# Omnimo_nRF52840_1v2.net
KiCad netlist of a schematic drawn in EasyEDA Pro
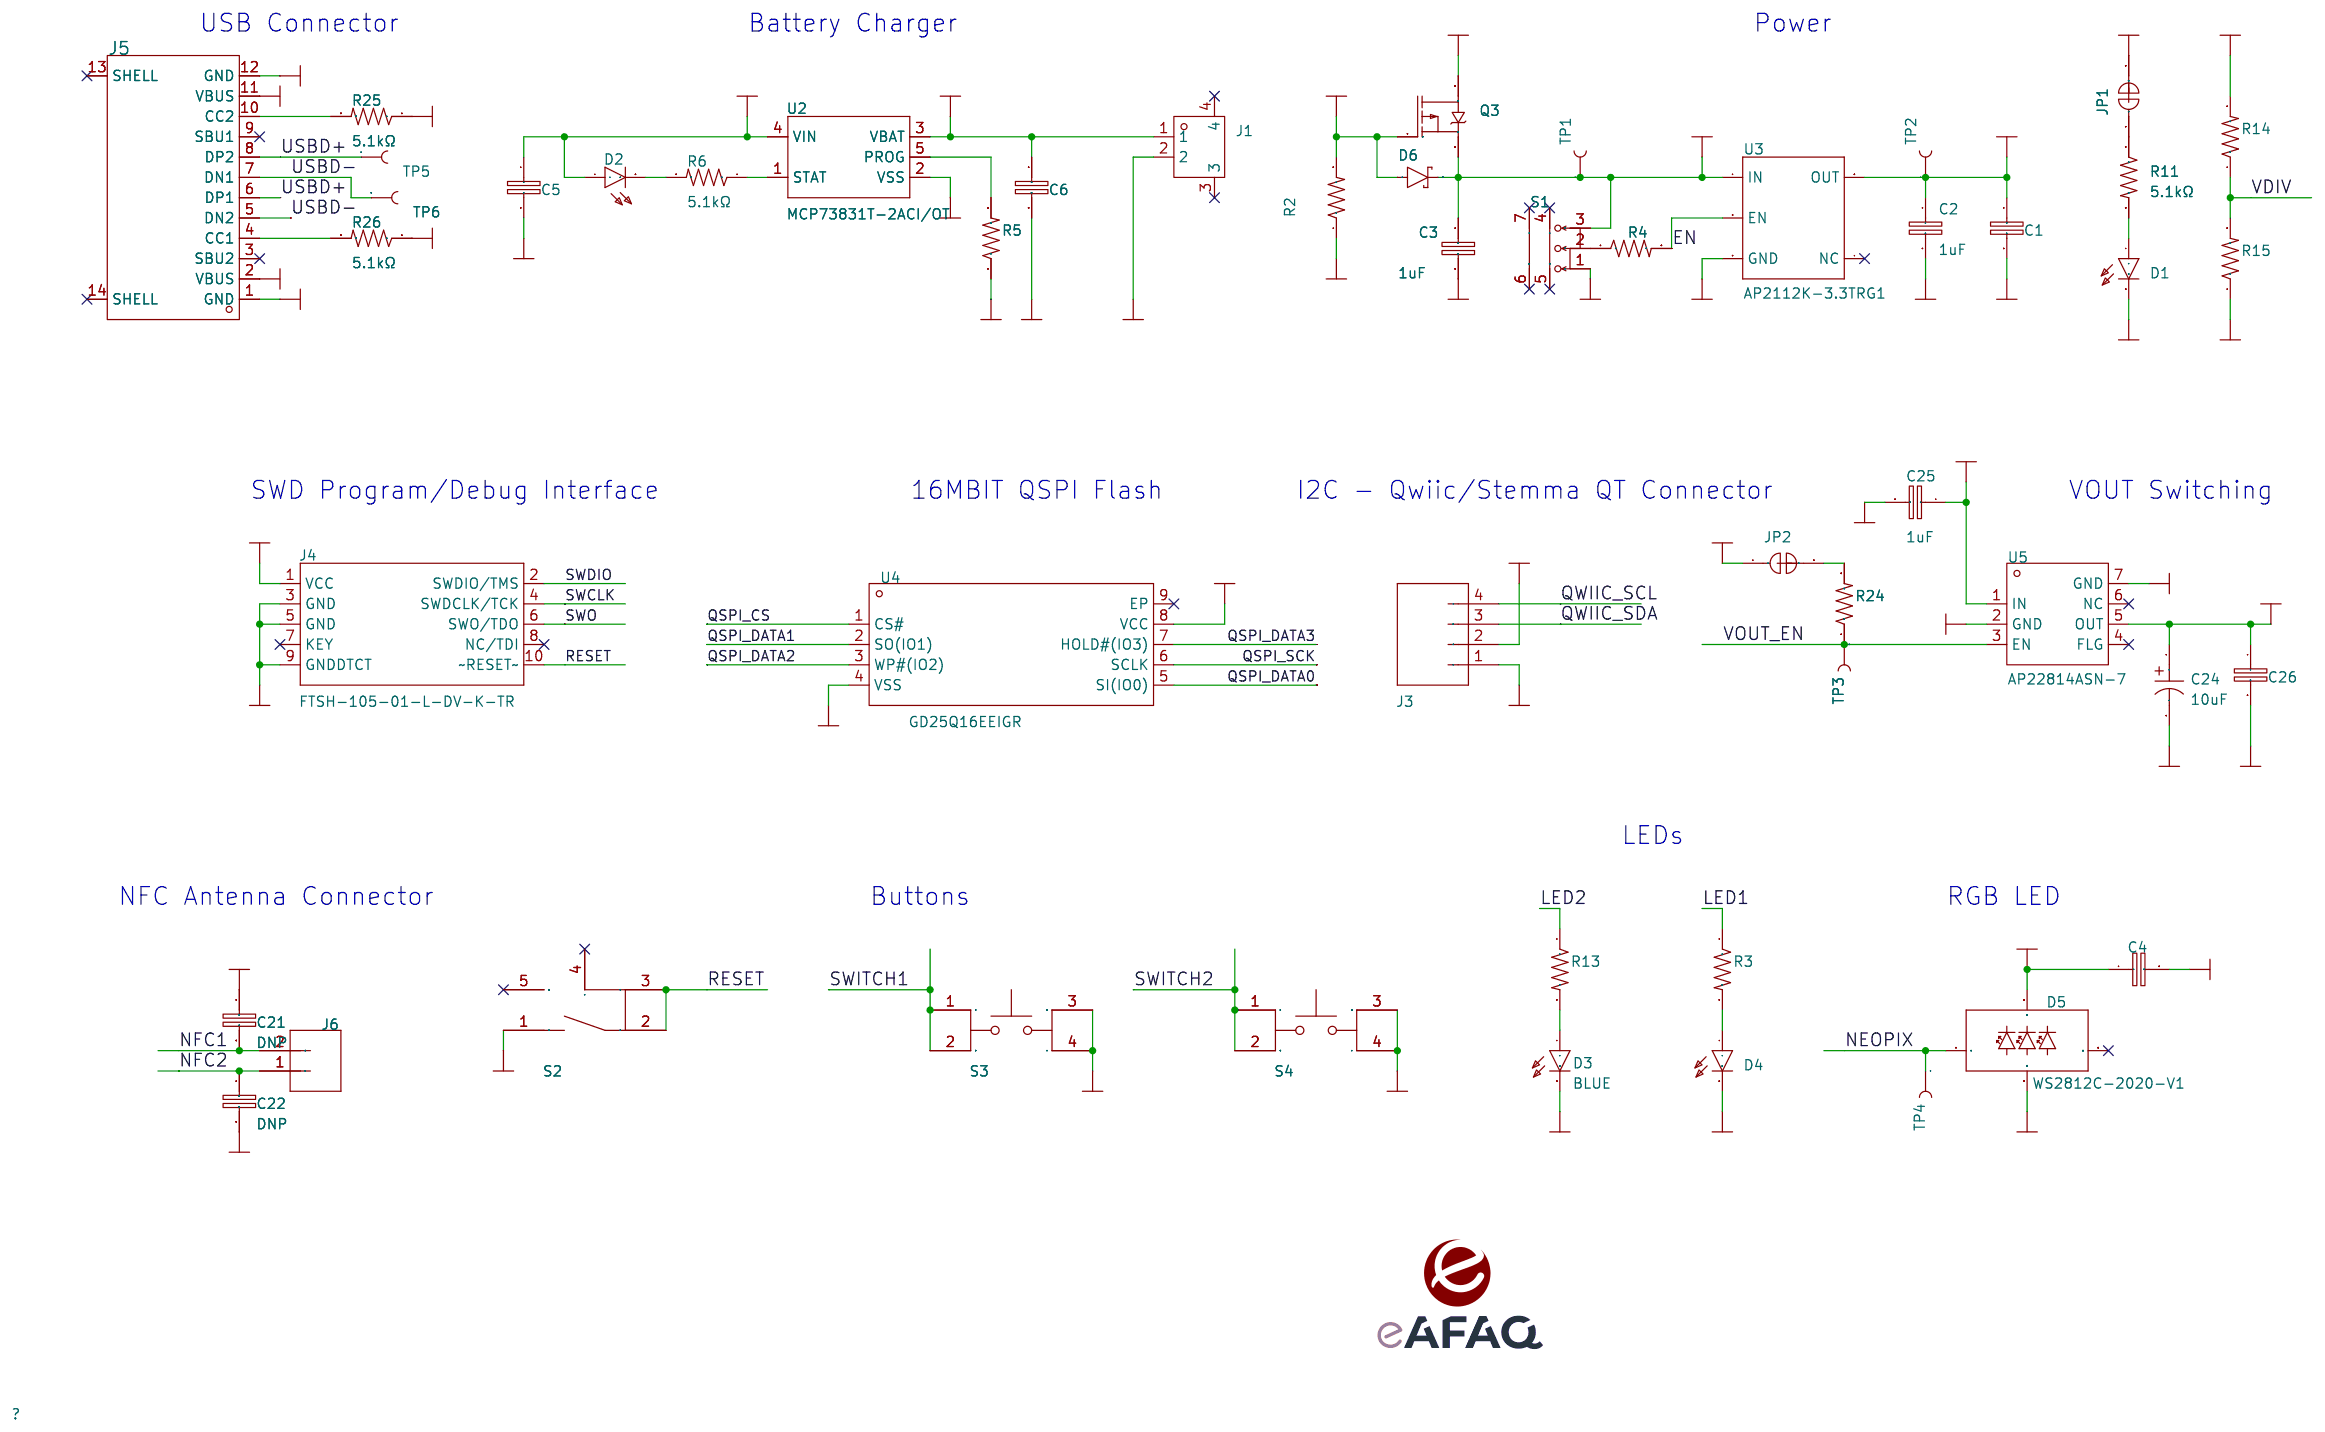
[diagram p0: Omnimo_nrf52840_v1_2_sheet_1]
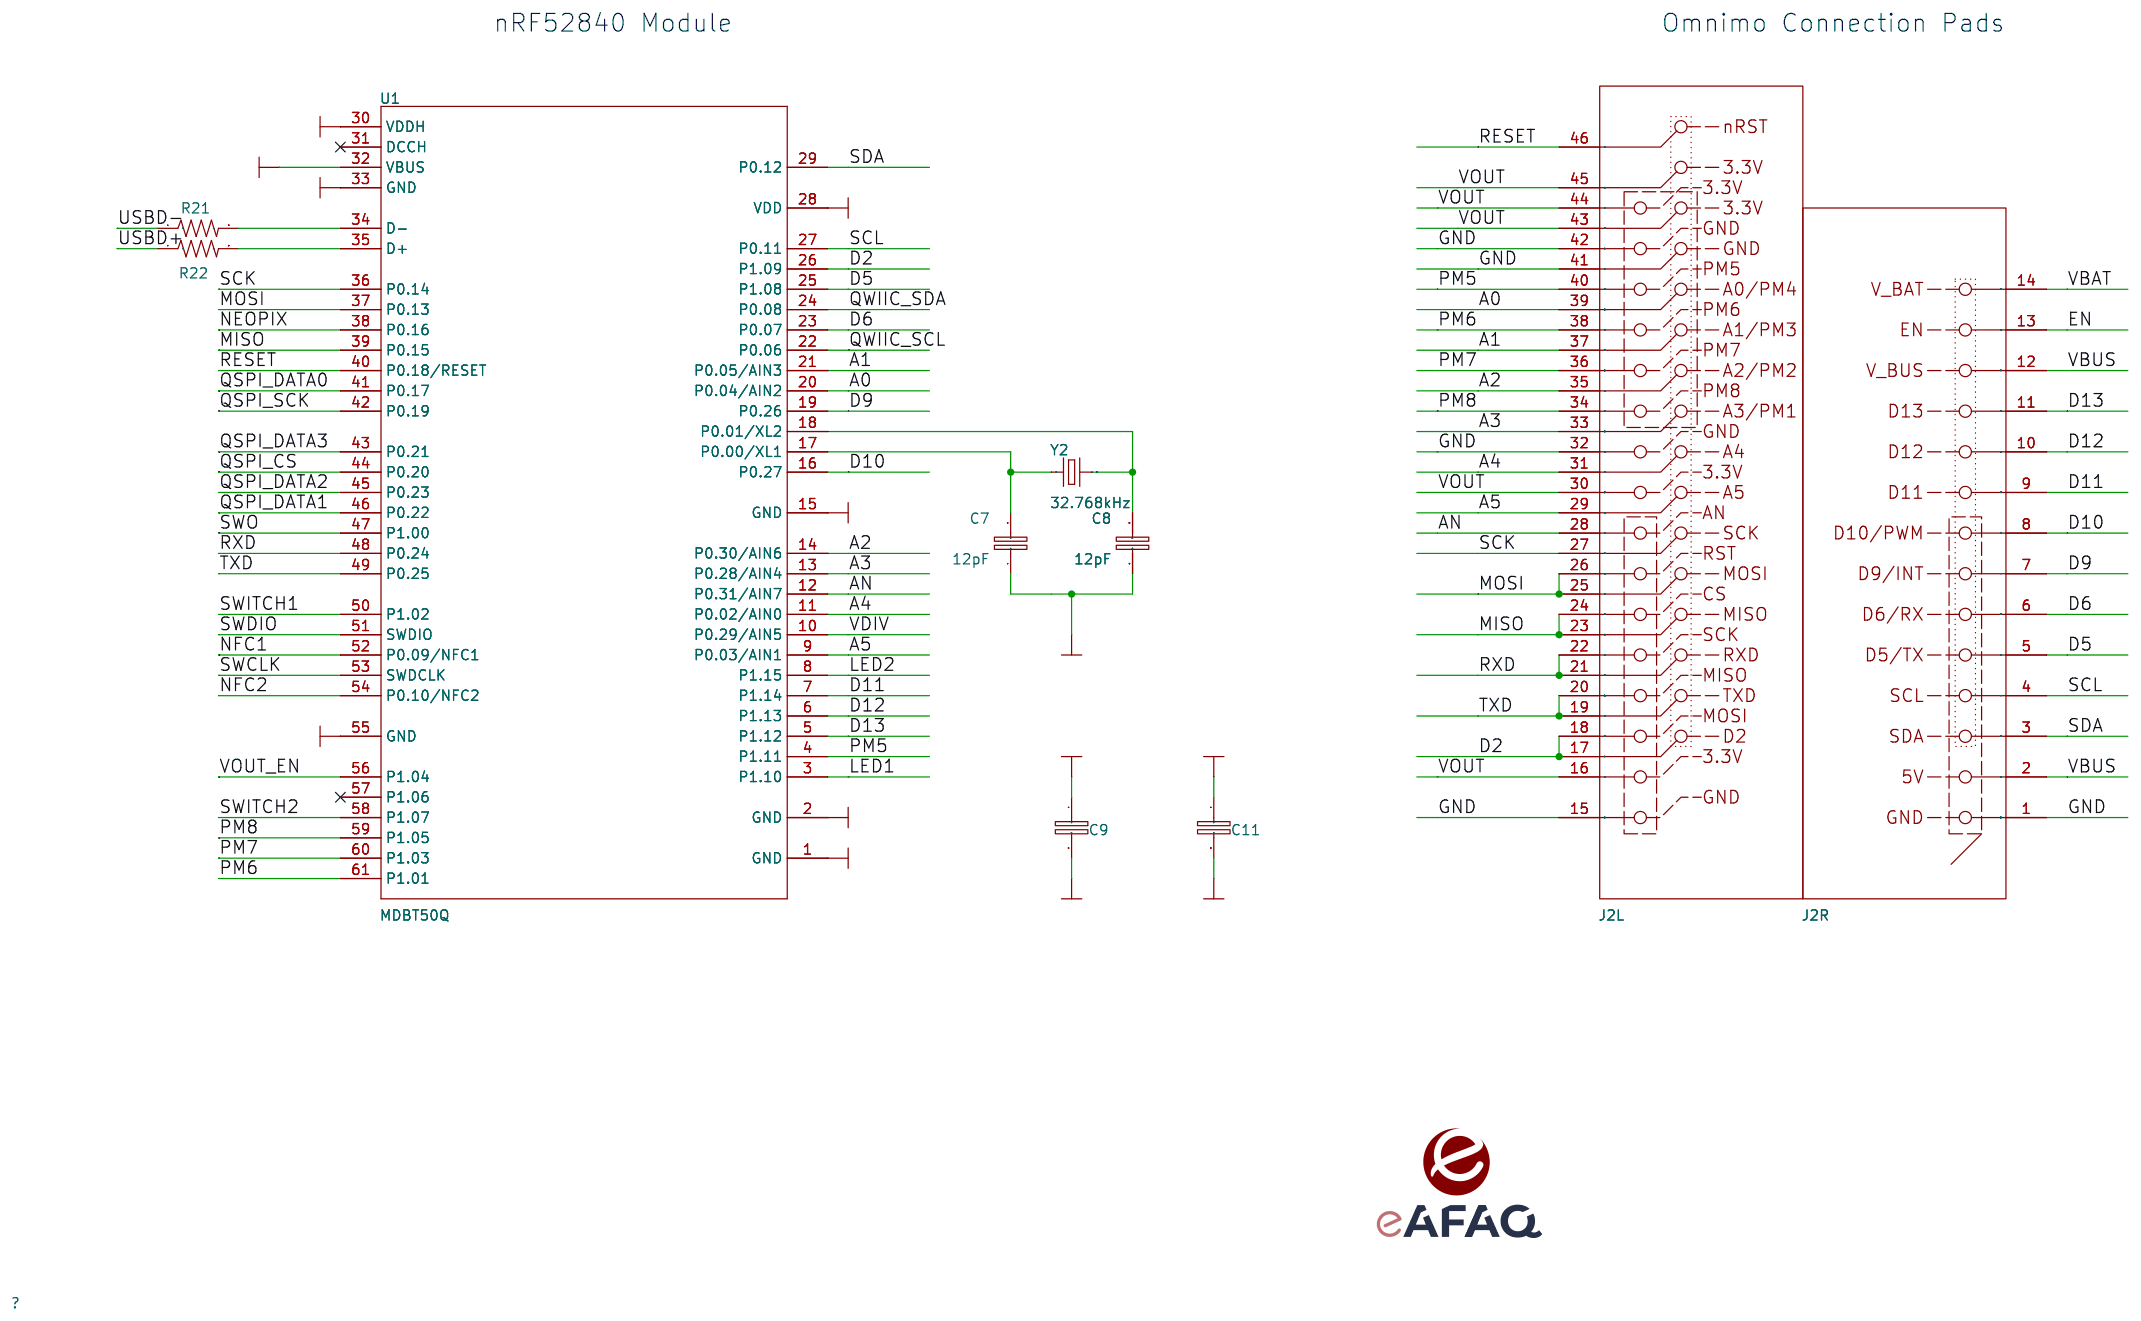
[diagram p1: Omnimo_nrf52840_v1_2_sheet_2]

(export (version "E")
  (design (tool "Eeschema 10.0.6"))
  (components
    (comp (ref "C1")
      (value "10uF")
      (footprint "easyedapro:0603_Nom")
      (fields (field (name "Manufacturer Part") "CC0603KRX5R5BB106"))
      (libsource (lib "easyedapro") (part "10UF-0603-6.3V-20%"))
    )
    (comp (ref "C2")
      (value "1uF")
      (fields
        (field (name "Manufacturer Part") "CL05A105KO5NNNC")
        (field (name "Manufacturer Part Number") "C0402C105K4PAC7867")
      )
      (libsource (lib "easyedapro") (part "1.0UF-0402T-16V-10%"))
    )
    (comp (ref "C3")
      (value "1uF")
      (fields
        (field (name "Manufacturer Part") "CL05A105KO5NNNC")
        (field (name "Manufacturer Part Number") "C0402C105K4PAC7867")
      )
      (libsource (lib "easyedapro") (part "1.0UF-0402T-16V-10%"))
    )
    (comp (ref "C4")
      (value "100nF")
      (fields
        (field (name "Manufacturer Part") "CC0402KRX5R6BB104")
        (field (name "Manufacturer Part Number") "C0402C104K8PACTU")
      )
      (libsource (lib "easyedapro") (part "0.1UF-0603-25V-(+80/-20%)"))
    )
    (comp (ref "C5")
      (value "4.7uF")
      (fields (field (name "Manufacturer Part") "CC0402MRX5R5BB475"))
      (libsource (lib "easyedapro") (part "4.7UF-0603-6.3V-(10%)"))
    )
    (comp (ref "C6")
      (value "4.7uF")
      (fields (field (name "Manufacturer Part") "CC0402MRX5R5BB475"))
      (libsource (lib "easyedapro") (part "4.7UF-0603-6.3V-(10%)"))
    )
    (comp (ref "C21")
      (value "DNP")
      (footprint "easyedapro:0603_Nom")
      (libsource (lib "easyedapro") (part "10UF-0603-6.3V-20%"))
    )
    (comp (ref "C22")
      (value "DNP")
      (footprint "easyedapro:0603_Nom")
      (libsource (lib "easyedapro") (part "10UF-0603-6.3V-20%"))
    )
    (comp (ref "C24")
      (value "10uF")
      (footprint "easyedapro:CAP-SMD_L1.6-W0.8")
      (description "10 µF Molded Tantalum Capacitors 6.3 V 0603 (1608 Metric) 10Ohm @ 100kHz")
      (fields (field (name "Manufacturer Part") "TMCJ0J106MTRF") (field (name "Manufacturer") "VISHAY(威世)"))
      (libsource (lib "easyedapro") (part "TMCJ0J106MTRF"))
    )
    (comp (ref "C25")
      (value "1uF")
      (fields
        (field (name "Manufacturer Part") "CL05A105KO5NNNC")
        (field (name "Manufacturer Part Number") "C0402C105K4PAC7867")
      )
      (libsource (lib "easyedapro") (part "1.0UF-0402T-16V-10%"))
    )
    (comp (ref "C26")
      (value "100nF")
      (fields
        (field (name "Manufacturer Part") "CC0402KRX5R6BB104")
        (field (name "Manufacturer Part Number") "C0402C104K8PACTU")
      )
      (libsource (lib "easyedapro") (part "0.1UF-0603-25V-(+80/-20%)"))
    )
    (comp (ref "D1")
      (value "RED")
      (fields
        (field (name "Manufacturer Part") "XL-1608SURC-06")
        (field (name "Manufacturer Part Number") "NCD1608W1")
      )
      (libsource (lib "easyedapro") (part "LED-YELLOW0603"))
    )
    (comp (ref "D2")
      (value "ORANGE")
      (fields
        (field (name "Manufacturer Part") "XL-1608UOC-06")
        (field (name "Manufacturer Part Number") "5988050107F")
      )
      (libsource (lib "easyedapro") (part "LED-YELLOW0603"))
    )
    (comp (ref "D3")
      (value "BLUE")
      (footprint "easyedapro:LED-0603_2")
      (fields
        (field (name "Manufacturer") "Dialight")
        (field (name "Manufacturer Part") "XL-1608UBC-04")
        (field (name "Manufacturer Part Number") "5988091107F")
      )
      (libsource (lib "easyedapro") (part "LED-BLUE0603"))
    )
    (comp (ref "D4")
      (value "RED")
      (fields
        (field (name "Manufacturer Part") "XL-1608SURC-06")
        (field (name "Manufacturer Part Number") "NCD1608W1")
      )
      (libsource (lib "easyedapro") (part "LED-YELLOW0603"))
    )
    (comp (ref "D5")
      (value "WS2812C-2020-V1")
      (description "Addressable Lighting Neopixel LED Discrete Red, Green, Blue (RGB) 2.00mm L x 2.00mm W")
      (fields (field (name "Manufacturer Part Number") "WS2812-2020"))
      (libsource (lib "easyedapro") (part "WS2812_2020"))
    )
    (comp (ref "D6")
      (value "BAT60B")
      (fields (field (name "Manufacturer Part Number") "BAT60AE6327HTSA1"))
      (libsource (lib "easyedapro") (part "DIODE-SCHOTTKY-BAT60A"))
    )
    (comp (ref "J1")
      (value "S2B-PH-SM4-TB(LF)(SN)")
      (footprint "easyedapro:CONN-SMD_P2.00_S2B-PH-SM4-TB-LF-SN")
      (fields
        (field (name "Manufacturer") "JST")
        (field (name "Manufacturer Part Number") "S2B-PH-SM4-K-TB (LF)(SN)")
      )
      (libsource (lib "easyedapro") (part "S2B-PH-SM4-TB(LF)(SN)"))
    )
    (comp (ref "J3")
      (value "SM04B-SRSS-TB(LF)(SN)")
      (libsource (lib "easyedapro") (part "JST-4-CONNECTOR-1MM"))
    )
    (comp (ref "J4") (value "FTSH-105-01-L-DV-K-TR") (libsource (lib "easyedapro") (part "CORTEX_DEBUG_PTH")))
    (comp (ref "J5")
      (value "TYPE-C 16PIN 2MD(073)")
      (footprint "easyedapro:USB-C-SMD_TYPE-C-6PIN-2MD-073")
      (fields (field (name "Manufacturer") "SHOU HAN(首韩)"))
      (libsource (lib "easyedapro") (part "TYPE-C 16PIN 2MD(073)"))
    )
    (comp (ref "J6")
      (value "CONN_021X02")
      (footprint "easyedapro:1X02_NFC")
      (libsource (lib "easyedapro") (part "CONN_021X02_NO_SILK"))
    )
    (comp (ref "JP1")
      (value "JUMPER-SMT_2_NC_TRACE_SILK")
      (footprint "easyedapro:SMT-JUMPER_2_NC_TRACE_SILK_2")
      (libsource (lib "easyedapro") (part "JUMPER-SMT_2_NC_TRACE_SILK"))
    )
    (comp (ref "JP2")
      (value "JUMPER-SMT_2_NC_TRACE_SILK")
      (footprint "easyedapro:SMT-JUMPER_2_NC_TRACE_SILK_2")
      (libsource (lib "easyedapro") (part "JUMPER-SMT_2_NC_TRACE_SILK"))
    )
    (comp (ref "Q3") (value "DMG2305UXQ-7") (libsource (lib "easyedapro") (part "MOSFET_PCH-DMG2305UX-7")))
    (comp (ref "R2")
      (value "100kΩ")
      (fields (field (name "Manufacturer Part") "RC0402FR-07100KL"))
      (libsource (lib "easyedapro") (part "10KOHM-0603-1/10W-1%"))
    )
    (comp (ref "R3")
      (value "2.2kΩ")
      (fields
        (field (name "Manufacturer Part") "RC0402FR-072K2L")
        (field (name "Manufacturer Part Number") "RC0402FR-071KL")
      )
      (libsource (lib "easyedapro") (part "1KOHM-0603-1/10W-1%"))
    )
    (comp (ref "R4")
      (value "100kΩ")
      (fields
        (field (name "Manufacturer Part") "RC0402FR-07100KL")
        (field (name "Manufacturer Part Number") "RC0402FR-0710KL")
      )
      (libsource (lib "easyedapro") (part "1KOHM-0603-1/10W-1%"))
    )
    (comp (ref "R5")
      (value "2kΩ")
      (fields (field (name "Manufacturer Part") "RC0402JR-072KL"))
      (libsource (lib "easyedapro") (part "2.0KOHM-0603-1/10W-5%"))
    )
    (comp (ref "R6")
      (value "5.1kΩ")
      (fields (field (name "Manufacturer Part") "RC0402FR-075K1L"))
      (libsource (lib "easyedapro") (part "5.1KOHM-0402T-1/16W-1%"))
    )
    (comp (ref "R11")
      (value "5.1kΩ")
      (fields (field (name "Manufacturer Part") "RC0402FR-075K1L"))
      (libsource (lib "easyedapro") (part "5.1KOHM-0402T-1/16W-1%"))
    )
    (comp (ref "R13")
      (value "2.2kΩ")
      (fields
        (field (name "Manufacturer Part") "RC0402FR-072K2L")
        (field (name "Manufacturer Part Number") "RC0402FR-071KL")
      )
      (libsource (lib "easyedapro") (part "1KOHM-0603-1/10W-1%"))
    )
    (comp (ref "R14")
      (value "100kΩ")
      (fields
        (field (name "Manufacturer Part") "RC0402DR-07100KL")
        (field (name "Manufacturer Part Number") "RC0402FR-07100KL")
      )
      (libsource (lib "easyedapro") (part "10KOHM-0603-1/10W-1%"))
    )
    (comp (ref "R15")
      (value "100kΩ")
      (fields
        (field (name "Manufacturer Part") "RC0402DR-07100KL")
        (field (name "Manufacturer Part Number") "RC0402FR-07100KL")
      )
      (libsource (lib "easyedapro") (part "10KOHM-0603-1/10W-1%"))
    )
    (comp (ref "R24")
      (value "100kΩ")
      (fields (field (name "Manufacturer Part") "RC0402FR-07100KL"))
      (libsource (lib "easyedapro") (part "10KOHM-0603-1/10W-1%"))
    )
    (comp (ref "R25")
      (value "5.1kΩ")
      (fields (field (name "Manufacturer Part") "RC0402FR-075K1L"))
      (libsource (lib "easyedapro") (part "5.1KOHM-0402T-1/16W-1%"))
    )
    (comp (ref "R26")
      (value "5.1kΩ")
      (fields (field (name "Manufacturer Part") "RC0402FR-075K1L"))
      (libsource (lib "easyedapro") (part "5.1KOHM-0402T-1/16W-1%"))
    )
    (comp (ref "S1")
      (value "TA-3514-A1-B")
      (footprint "easyedapro:SW-SMD_TA-3514-A1-B")
      (fields (field (name "Manufacturer") "Yuandi(元迪)"))
      (libsource (lib "easyedapro") (part "TA-3514-A1-B"))
    )
    (comp (ref "S2") (value "R-667270") (libsource (lib "easyedapro") (part "Tact Switch - PTS815 Series_1")))
    (comp (ref "S3")
      (value "PTS815SJG250SMTRLFS")
      (fields (field (name "Manufacturer Part Number") "PTS815SJM250SMTRLFS"))
      (libsource (lib "easyedapro") (part "Tact Switch - PTS815 Series"))
    )
    (comp (ref "S4")
      (value "PTS815SJG250SMTRLFS")
      (fields (field (name "Manufacturer Part Number") "PTS815SJM250SMTRLFS"))
      (libsource (lib "easyedapro") (part "Tact Switch - PTS815 Series"))
    )
    (comp (ref "TP1")
      (value "TEST-POINT3X5")
      (footprint "easyedapro:TEST_POINT_1mm")
      (description "Test Point")
      (libsource (lib "easyedapro") (part "TEST-POINT3X5"))
    )
    (comp (ref "TP2")
      (value "TEST-POINT3X5")
      (footprint "easyedapro:TEST_POINT_1mm")
      (description "Test Point")
      (libsource (lib "easyedapro") (part "TEST-POINT3X5"))
    )
    (comp (ref "TP3")
      (value "TEST-POINT3X5")
      (footprint "easyedapro:TEST_POINT_1mm")
      (description "Test Point")
      (libsource (lib "easyedapro") (part "TEST-POINT3X5"))
    )
    (comp (ref "TP4")
      (value "TEST-POINT3X5")
      (footprint "easyedapro:TEST_POINT_1mm")
      (description "Test Point")
      (libsource (lib "easyedapro") (part "TEST-POINT3X5"))
    )
    (comp (ref "TP5")
      (value "TEST-POINT3X5")
      (footprint "easyedapro:TEST_POINT_1mm")
      (description "Test Point")
      (libsource (lib "easyedapro") (part "TEST-POINT3X5"))
    )
    (comp (ref "TP6")
      (value "TEST-POINT3X5")
      (footprint "easyedapro:TEST_POINT_1mm")
      (description "Test Point")
      (libsource (lib "easyedapro") (part "TEST-POINT3X5"))
    )
    (comp (ref "U2") (value "MCP73831T-2ACI/OT") (libsource (lib "easyedapro") (part "MCP73831")))
    (comp (ref "U3") (value "AP2112K-3.3TRG1") (libsource (lib "easyedapro") (part "V_REG_AP2112K-3.3V")))
    (comp (ref "U4")
      (value "GD25Q16EEIGR")
      (footprint "easyedapro:USON-8_L3.0-W2.0-P0.50-BL-EP_GD25QXX")
      (fields
        (field (name "Manufacturer") "GigaDevice(兆易创新)")
        (field (name "Manufacturer Part Number") "GD25WQ16EEIGR")
      )
      (libsource (lib "easyedapro") (part "GD25Q16EEIGR"))
    )
    (comp (ref "U5")
      (value "AP22814ASN-7")
      (footprint "easyedapro:U-DFN2020-6_L2.0-W2.0-P0.65-BL-EP")
      (description "Power Switch/Driver 1:1 P-Channel 3A U-DFN2020-6")
      (fields (field (name "Manufacturer") "DIODES(美台)"))
      (libsource (lib "easyedapro") (part "AP22804ASN-7"))
    )
    (comp (ref "C7")
      (value "12pF")
      (footprint "easyedapro:0402_NOM")
      (description "12pF, 0402, 50V, 1%")
      (fields (field (name "Manufacturer") "AVX") (field (name "Manufacturer Part") "04025U120FAT2A"))
      (libsource (lib "easyedapro") (part "15PF-0603-50V-5%"))
    )
    (comp (ref "C8")
      (value "12pF")
      (footprint "easyedapro:0402_NOM")
      (description "12pF, 0402, 50V, 1%")
      (fields (field (name "Manufacturer") "AVX") (field (name "Manufacturer Part") "04025U120FAT2A"))
      (libsource (lib "easyedapro") (part "15PF-0603-50V-5%"))
    )
    (comp (ref "C9")
      (value "10uF")
      (footprint "easyedapro:0603_Nom")
      (fields (field (name "Manufacturer Part") "CC0603KRX5R5BB106"))
      (libsource (lib "easyedapro") (part "10UF-0603-6.3V-20%"))
    )
    (comp (ref "C11")
      (value "100nF")
      (fields
        (field (name "Manufacturer Part") "CC0402KRX5R6BB104")
        (field (name "Manufacturer Part Number") "C0402C104K8PACTU")
      )
      (libsource (lib "easyedapro") (part "0.1UF-0603-25V-(+80/-20%)"))
    )
    (comp (ref "J2L")
      (value "omnimo_Header_left")
      (footprint "easyedapro:Omnimo_HDR_Left_nRF52_2 - without silk screen")
      (libsource (lib "easyedapro") (part "omnimo_HDR_Left"))
    )
    (comp (ref "J2R")
      (value "omnimo_Header_right")
      (footprint "easyedapro:Omnimo_HDR_Right_nRF52_2 - without silk screen")
      (libsource (lib "easyedapro") (part "omnimo_HDR_Right"))
    )
    (comp (ref "R21")
      (value "27Ω")
      (footprint "easyedapro:0402_NOM")
      (description "RES 27 OHM 1% 1/10W 0402 SMD")
      (fields
        (field (name "Manufacturer") "Panasonic Electronic Components")
        (field (name "Manufacturer Part") "ERJ-U02F27R0X")
      )
      (libsource (lib "easyedapro") (part "27OHM-0603-1/10W-1%"))
    )
    (comp (ref "R22")
      (value "27Ω")
      (footprint "easyedapro:0402_NOM")
      (description "RES 27 OHM 1% 1/10W 0402 SMD")
      (fields
        (field (name "Manufacturer") "Panasonic Electronic Components")
        (field (name "Manufacturer Part") "ERJ-U02F27R0X")
      )
      (libsource (lib "easyedapro") (part "27OHM-0603-1/10W-1%"))
    )
    (comp (ref "U1")
      (value "MDBT50Q")
      (footprint "easyedapro:MDBT50Q-1MV2")
      (description "MDBT50 Bluetooth Low Energy Module based on Noridc nRF52840")
      (fields (field (name "Manufacturer") "Raytac") (field (name "Manufacturer Part") "MDBT50Q-1MV2"))
      (libsource (lib "easyedapro") (part "MDBT50Q"))
    )
    (comp (ref "Y2")
      (value "32.768kHz")
      (fields (field (name "Manufacturer Part") "ABS07-32.768KHZ-T"))
      (libsource (lib "easyedapro") (part "CRYSTAL-32.768KHZSMD-3.2X1.5"))
    )
  )
  (nets
    (net (code "1") (name "3.3V") (class "Default")
      (node (ref "C1") (pin "1") (pinfunction "1_1") (pintype "unspecified"))
      (node (ref "C11") (pin "1") (pinfunction "1_1") (pintype "unspecified"))
      (node (ref "C2") (pin "1") (pinfunction "1_1") (pintype "unspecified"))
      (node (ref "C25") (pin "1") (pinfunction "1_1") (pintype "unspecified"))
      (node (ref "C9") (pin "1") (pinfunction "1_1") (pintype "unspecified"))
      (node (ref "J4") (pin "1") (pinfunction "VCC_1") (pintype "unspecified"))
      (node (ref "JP1") (pin "2") (pinfunction "2_2") (pintype "unspecified"))
      (node (ref "JP2") (pin "1") (pinfunction "1_1") (pintype "unspecified"))
      (node (ref "TP2") (pin "P$1") (pinfunction "1_P$1") (pintype "unspecified"))
      (node (ref "U1") (pin "28") (pinfunction "VDD_28") (pintype "unspecified"))
      (node (ref "U1") (pin "30") (pinfunction "VDDH_30") (pintype "unspecified"))
      (node (ref "U3") (pin "5") (pinfunction "OUT_5") (pintype "unspecified"))
      (node (ref "U4") (pin "8") (pinfunction "VCC_8") (pintype "unspecified"))
      (node (ref "U5") (pin "1") (pinfunction "IN_1") (pintype "input"))
    )
    (net (code "2") (name "A0") (class "Default")
      (node (ref "J2L") (pin "39") (pinfunction "39_39") (pintype "unspecified"))
      (node (ref "U1") (pin "20") (pinfunction "P0.04/AIN2_20") (pintype "unspecified"))
    )
    (net (code "3") (name "A1") (class "Default")
      (node (ref "J2L") (pin "37") (pinfunction "37_37") (pintype "unspecified"))
      (node (ref "U1") (pin "21") (pinfunction "P0.05/AIN3_21") (pintype "unspecified"))
    )
    (net (code "4") (name "A2") (class "Default")
      (node (ref "J2L") (pin "35") (pinfunction "35_35") (pintype "unspecified"))
      (node (ref "U1") (pin "14") (pinfunction "P0.30/AIN6_14") (pintype "unspecified"))
    )
    (net (code "5") (name "A3") (class "Default")
      (node (ref "J2L") (pin "33") (pinfunction "33_33") (pintype "unspecified"))
      (node (ref "U1") (pin "13") (pinfunction "P0.28/AIN4_13") (pintype "unspecified"))
    )
    (net (code "6") (name "A4") (class "Default")
      (node (ref "J2L") (pin "31") (pinfunction "31_31") (pintype "unspecified"))
      (node (ref "U1") (pin "11") (pinfunction "P0.02/AIN0_11") (pintype "unspecified"))
    )
    (net (code "7") (name "A5") (class "Default")
      (node (ref "J2L") (pin "29") (pinfunction "29_29") (pintype "unspecified"))
      (node (ref "U1") (pin "9") (pinfunction "P0.03/AIN1_9") (pintype "unspecified"))
    )
    (net (code "8") (name "AN") (class "Default")
      (node (ref "J2L") (pin "28") (pinfunction "28_28") (pintype "unspecified"))
      (node (ref "U1") (pin "12") (pinfunction "P0.31/AIN7_12") (pintype "unspecified"))
    )
    (net (code "9") (name "D2") (class "Default")
      (node (ref "J2L") (pin "17") (pinfunction "17_17") (pintype "unspecified"))
      (node (ref "J2L") (pin "18") (pinfunction "18_18") (pintype "unspecified"))
      (node (ref "U1") (pin "26") (pinfunction "P1.09_26") (pintype "unspecified"))
    )
    (net (code "10") (name "D5") (class "Default")
      (node (ref "J2R") (pin "5") (pinfunction "5_5") (pintype "unspecified"))
      (node (ref "U1") (pin "25") (pinfunction "P1.08_25") (pintype "unspecified"))
    )
    (net (code "11") (name "D6") (class "Default")
      (node (ref "J2R") (pin "6") (pinfunction "6_6") (pintype "unspecified"))
      (node (ref "U1") (pin "23") (pinfunction "P0.07_23") (pintype "unspecified"))
    )
    (net (code "12") (name "D9") (class "Default")
      (node (ref "J2R") (pin "7") (pinfunction "7_7") (pintype "unspecified"))
      (node (ref "U1") (pin "19") (pinfunction "P0.26_19") (pintype "unspecified"))
    )
    (net (code "13") (name "D10") (class "Default")
      (node (ref "J2R") (pin "8") (pinfunction "8_8") (pintype "unspecified"))
      (node (ref "U1") (pin "16") (pinfunction "P0.27_16") (pintype "unspecified"))
    )
    (net (code "14") (name "D11") (class "Default")
      (node (ref "J2R") (pin "9") (pinfunction "9_9") (pintype "unspecified"))
      (node (ref "U1") (pin "7") (pinfunction "P1.14_7") (pintype "unspecified"))
    )
    (net (code "15") (name "D12") (class "Default")
      (node (ref "J2R") (pin "10") (pinfunction "10_10") (pintype "unspecified"))
      (node (ref "U1") (pin "6") (pinfunction "P1.13_6") (pintype "unspecified"))
    )
    (net (code "16") (name "D13") (class "Default")
      (node (ref "J2R") (pin "11") (pinfunction "11_11") (pintype "unspecified"))
      (node (ref "U1") (pin "5") (pinfunction "P1.12_5") (pintype "unspecified"))
    )
    (net (code "17") (name "EN") (class "Default")
      (node (ref "J2R") (pin "13") (pinfunction "13_13") (pintype "unspecified"))
      (node (ref "R4") (pin "2") (pinfunction "2_2") (pintype "unspecified"))
      (node (ref "U3") (pin "3") (pinfunction "EN_3") (pintype "unspecified"))
    )
    (net (code "18") (name "GND") (class "Default")
      (node (ref "C1") (pin "2") (pinfunction "2_2") (pintype "unspecified"))
      (node (ref "C11") (pin "2") (pinfunction "2_2") (pintype "unspecified"))
      (node (ref "C2") (pin "2") (pinfunction "2_2") (pintype "unspecified"))
      (node (ref "C21") (pin "1") (pinfunction "1_1") (pintype "unspecified"))
      (node (ref "C22") (pin "2") (pinfunction "2_2") (pintype "unspecified"))
      (node (ref "C24") (pin "2") (pinfunction "2_2") (pintype "input"))
      (node (ref "C25") (pin "2") (pinfunction "2_2") (pintype "unspecified"))
      (node (ref "C26") (pin "2") (pinfunction "2_2") (pintype "unspecified"))
      (node (ref "C3") (pin "2") (pinfunction "2_2") (pintype "unspecified"))
      (node (ref "C4") (pin "2") (pinfunction "2_2") (pintype "unspecified"))
      (node (ref "C5") (pin "2") (pinfunction "2_2") (pintype "unspecified"))
      (node (ref "C6") (pin "2") (pinfunction "2_2") (pintype "unspecified"))
      (node (ref "C7") (pin "1") (pinfunction "1_1") (pintype "unspecified"))
      (node (ref "C8") (pin "1") (pinfunction "1_1") (pintype "unspecified"))
      (node (ref "C9") (pin "2") (pinfunction "2_2") (pintype "unspecified"))
      (node (ref "D1") (pin "C") (pinfunction "C_C") (pintype "unspecified"))
      (node (ref "D3") (pin "C") (pinfunction "C_C") (pintype "unspecified"))
      (node (ref "D4") (pin "C") (pinfunction "C_C") (pintype "unspecified"))
      (node (ref "D5") (pin "GND") (pinfunction "GND_GND") (pintype "unspecified"))
      (node (ref "J1") (pin "2") (pinfunction "2_2") (pintype "unspecified"))
      (node (ref "J2L") (pin "15") (pinfunction "15_15") (pintype "unspecified"))
      (node (ref "J2L") (pin "32") (pinfunction "32_32") (pintype "unspecified"))
      (node (ref "J2L") (pin "41") (pinfunction "41_41") (pintype "unspecified"))
      (node (ref "J2L") (pin "42") (pinfunction "42_42") (pintype "unspecified"))
      (node (ref "J2R") (pin "1") (pinfunction "GND_1") (pintype "unspecified"))
      (node (ref "J3") (pin "1") (pinfunction "1_1") (pintype "unspecified"))
      (node (ref "J4") (pin "3") (pinfunction "GND_3") (pintype "unspecified"))
      (node (ref "J4") (pin "5") (pinfunction "GND_5") (pintype "unspecified"))
      (node (ref "J4") (pin "9") (pinfunction "GNDDTCT_9") (pintype "unspecified"))
      (node (ref "J5") (pin "1") (pinfunction "GND_1") (pintype "input"))
      (node (ref "J5") (pin "12") (pinfunction "GND_12") (pintype "input"))
      (node (ref "R15") (pin "1") (pinfunction "1_1") (pintype "unspecified"))
      (node (ref "R2") (pin "1") (pinfunction "1_1") (pintype "unspecified"))
      (node (ref "R25") (pin "1") (pinfunction "1_1") (pintype "unspecified"))
      (node (ref "R26") (pin "1") (pinfunction "1_1") (pintype "unspecified"))
      (node (ref "R5") (pin "1") (pinfunction "1_1") (pintype "unspecified"))
      (node (ref "S1") (pin "1") (pinfunction "1_1") (pintype "unspecified"))
      (node (ref "S2") (pin "1") (pinfunction "1_1") (pintype "unspecified"))
      (node (ref "S3") (pin "3") (pinfunction "3_3") (pintype "unspecified"))
      (node (ref "S3") (pin "4") (pinfunction "4_4") (pintype "unspecified"))
      (node (ref "S4") (pin "3") (pinfunction "3_3") (pintype "unspecified"))
      (node (ref "S4") (pin "4") (pinfunction "4_4") (pintype "unspecified"))
      (node (ref "U1") (pin "1") (pinfunction "GND_1") (pintype "unspecified"))
      (node (ref "U1") (pin "15") (pinfunction "GND_15") (pintype "unspecified"))
      (node (ref "U1") (pin "2") (pinfunction "GND_2") (pintype "unspecified"))
      (node (ref "U1") (pin "33") (pinfunction "GND_33") (pintype "unspecified"))
      (node (ref "U1") (pin "55") (pinfunction "GND_55") (pintype "unspecified"))
      (node (ref "U2") (pin "2") (pinfunction "VSS_2") (pintype "unspecified"))
      (node (ref "U3") (pin "2") (pinfunction "GND_2") (pintype "unspecified"))
      (node (ref "U4") (pin "4") (pinfunction "VSS_4") (pintype "unspecified"))
      (node (ref "U5") (pin "2") (pinfunction "GND_2") (pintype "input"))
      (node (ref "U5") (pin "7") (pinfunction "GND_7") (pintype "input"))
    )
    (net (code "19") (name "LED1") (class "Default")
      (node (ref "R3") (pin "1") (pinfunction "1_1") (pintype "unspecified"))
      (node (ref "U1") (pin "3") (pinfunction "P1.10_3") (pintype "unspecified"))
    )
    (net (code "20") (name "LED2") (class "Default")
      (node (ref "R13") (pin "1") (pinfunction "1_1") (pintype "unspecified"))
      (node (ref "U1") (pin "8") (pinfunction "P1.15_8") (pintype "unspecified"))
    )
    (net (code "21") (name "MISO") (class "Default")
      (node (ref "J2L") (pin "23") (pinfunction "23_23") (pintype "unspecified"))
      (node (ref "J2L") (pin "24") (pinfunction "24_24") (pintype "unspecified"))
      (node (ref "U1") (pin "39") (pinfunction "P0.15_39") (pintype "unspecified"))
    )
    (net (code "22") (name "MOSI") (class "Default")
      (node (ref "J2L") (pin "25") (pinfunction "25_25") (pintype "unspecified"))
      (node (ref "J2L") (pin "26") (pinfunction "26_26") (pintype "unspecified"))
      (node (ref "U1") (pin "37") (pinfunction "P0.13_37") (pintype "unspecified"))
    )
    (net (code "23") (name "NEOPIX") (class "Default")
      (node (ref "D5") (pin "DI") (pinfunction "DI_DI") (pintype "unspecified"))
      (node (ref "TP4") (pin "P$1") (pinfunction "1_P$1") (pintype "unspecified"))
      (node (ref "U1") (pin "38") (pinfunction "P0.16_38") (pintype "unspecified"))
    )
    (net (code "24") (name "NFC1") (class "Default")
      (node (ref "C21") (pin "2") (pinfunction "2_2") (pintype "unspecified"))
      (node (ref "J6") (pin "2") (pinfunction "2_2") (pintype "unspecified"))
      (node (ref "U1") (pin "52") (pinfunction "P0.09/NFC1_52") (pintype "unspecified"))
    )
    (net (code "25") (name "NFC2") (class "Default")
      (node (ref "C22") (pin "1") (pinfunction "1_1") (pintype "unspecified"))
      (node (ref "J6") (pin "1") (pinfunction "1_1") (pintype "unspecified"))
      (node (ref "U1") (pin "54") (pinfunction "P0.10/NFC2_54") (pintype "unspecified"))
    )
    (net (code "26") (name "Net-(D1-PadA)") (class "Default")
      (node (ref "D1") (pin "A") (pinfunction "A_A") (pintype "unspecified"))
      (node (ref "R11") (pin "2") (pinfunction "2_2") (pintype "unspecified"))
    )
    (net (code "27") (name "Net-(D2-PadC)") (class "Default")
      (node (ref "D2") (pin "C") (pinfunction "C_C") (pintype "unspecified"))
      (node (ref "R6") (pin "2") (pinfunction "2_2") (pintype "unspecified"))
    )
    (net (code "28") (name "Net-(D3-PadA)") (class "Default")
      (node (ref "D3") (pin "A") (pinfunction "A_A") (pintype "unspecified"))
      (node (ref "R13") (pin "2") (pinfunction "2_2") (pintype "unspecified"))
    )
    (net (code "29") (name "Net-(D4-PadA)") (class "Default")
      (node (ref "D4") (pin "A") (pinfunction "A_A") (pintype "unspecified"))
      (node (ref "R3") (pin "2") (pinfunction "2_2") (pintype "unspecified"))
    )
    (net (code "30") (name "Net-(J5-CC1)") (class "Default")
      (node (ref "J5") (pin "4") (pinfunction "CC1_4") (pintype "input"))
      (node (ref "R26") (pin "2") (pinfunction "2_2") (pintype "unspecified"))
    )
    (net (code "31") (name "Net-(J5-CC2)") (class "Default")
      (node (ref "J5") (pin "10") (pinfunction "CC2_10") (pintype "input"))
      (node (ref "R25") (pin "2") (pinfunction "2_2") (pintype "unspecified"))
    )
    (net (code "32") (name "Net-(JP1-Pad1)") (class "Default")
      (node (ref "JP1") (pin "1") (pinfunction "1_1") (pintype "unspecified"))
      (node (ref "R11") (pin "1") (pinfunction "1_1") (pintype "unspecified"))
    )
    (net (code "33") (name "Net-(JP2-Pad2)") (class "Default")
      (node (ref "JP2") (pin "2") (pinfunction "2_2") (pintype "unspecified"))
      (node (ref "R24") (pin "2") (pinfunction "2_2") (pintype "unspecified"))
    )
    (net (code "34") (name "Net-(R4-Pad1)") (class "Default")
      (node (ref "R4") (pin "1") (pinfunction "1_1") (pintype "unspecified"))
      (node (ref "S1") (pin "2") (pinfunction "2_2") (pintype "unspecified"))
    )
    (net (code "35") (name "Net-(U1-D+)") (class "Default")
      (node (ref "R22") (pin "2") (pinfunction "2_2") (pintype "unspecified"))
      (node (ref "U1") (pin "35") (pinfunction "D+_35") (pintype "unspecified"))
    )
    (net (code "36") (name "Net-(U1-D-)") (class "Default")
      (node (ref "R21") (pin "2") (pinfunction "2_2") (pintype "unspecified"))
      (node (ref "U1") (pin "34") (pinfunction "D-_34") (pintype "unspecified"))
    )
    (net (code "37") (name "Net-(U1-P0.00{slash}XL1)") (class "Default")
      (node (ref "C7") (pin "2") (pinfunction "2_2") (pintype "unspecified"))
      (node (ref "U1") (pin "17") (pinfunction "P0.00/XL1_17") (pintype "unspecified"))
      (node (ref "Y2") (pin "P$1") (pinfunction "1_P$1") (pintype "unspecified"))
    )
    (net (code "38") (name "Net-(U1-P0.01{slash}XL2)") (class "Default")
      (node (ref "C8") (pin "2") (pinfunction "2_2") (pintype "unspecified"))
      (node (ref "U1") (pin "18") (pinfunction "P0.01/XL2_18") (pintype "unspecified"))
      (node (ref "Y2") (pin "P$2") (pinfunction "2_P$2") (pintype "unspecified"))
    )
    (net (code "39") (name "Net-(U2-PROG)") (class "Default")
      (node (ref "R5") (pin "2") (pinfunction "2_2") (pintype "unspecified"))
      (node (ref "U2") (pin "5") (pinfunction "PROG_5") (pintype "unspecified"))
    )
    (net (code "40") (name "Net-(U2-STAT)") (class "Default")
      (node (ref "R6") (pin "1") (pinfunction "1_1") (pintype "unspecified"))
      (node (ref "U2") (pin "1") (pinfunction "STAT_1") (pintype "output"))
    )
    (net (code "41") (name "PM5") (class "Default")
      (node (ref "J2L") (pin "40") (pinfunction "40_40") (pintype "unspecified"))
      (node (ref "U1") (pin "4") (pinfunction "P1.11_4") (pintype "unspecified"))
    )
    (net (code "42") (name "PM6") (class "Default")
      (node (ref "J2L") (pin "38") (pinfunction "38_38") (pintype "unspecified"))
      (node (ref "U1") (pin "61") (pinfunction "P1.01_61") (pintype "unspecified"))
    )
    (net (code "43") (name "PM7") (class "Default")
      (node (ref "J2L") (pin "36") (pinfunction "36_36") (pintype "unspecified"))
      (node (ref "U1") (pin "60") (pinfunction "P1.03_60") (pintype "unspecified"))
    )
    (net (code "44") (name "PM8") (class "Default")
      (node (ref "J2L") (pin "34") (pinfunction "34_34") (pintype "unspecified"))
      (node (ref "U1") (pin "59") (pinfunction "P1.05_59") (pintype "unspecified"))
    )
    (net (code "45") (name "QSPI_CS") (class "Default")
      (node (ref "U1") (pin "44") (pinfunction "P0.20_44") (pintype "unspecified"))
      (node (ref "U4") (pin "1") (pinfunction "CS#_1") (pintype "unspecified"))
    )
    (net (code "46") (name "QSPI_DATA0") (class "Default")
      (node (ref "U1") (pin "41") (pinfunction "P0.17_41") (pintype "unspecified"))
      (node (ref "U4") (pin "5") (pinfunction "SI(IO0)_5") (pintype "unspecified"))
    )
    (net (code "47") (name "QSPI_DATA1") (class "Default")
      (node (ref "U1") (pin "46") (pinfunction "P0.22_46") (pintype "unspecified"))
      (node (ref "U4") (pin "2") (pinfunction "SO(IO1)_2") (pintype "unspecified"))
    )
    (net (code "48") (name "QSPI_DATA2") (class "Default")
      (node (ref "U1") (pin "45") (pinfunction "P0.23_45") (pintype "unspecified"))
      (node (ref "U4") (pin "3") (pinfunction "WP#(IO2)_3") (pintype "unspecified"))
    )
    (net (code "49") (name "QSPI_DATA3") (class "Default")
      (node (ref "U1") (pin "43") (pinfunction "P0.21_43") (pintype "unspecified"))
      (node (ref "U4") (pin "7") (pinfunction "HOLD#(IO3)_7") (pintype "unspecified"))
    )
    (net (code "50") (name "QSPI_SCK") (class "Default")
      (node (ref "U1") (pin "42") (pinfunction "P0.19_42") (pintype "unspecified"))
      (node (ref "U4") (pin "6") (pinfunction "SCLK_6") (pintype "unspecified"))
    )
    (net (code "51") (name "QWIIC_SCL") (class "Default")
      (node (ref "J3") (pin "4") (pinfunction "4_4") (pintype "unspecified"))
      (node (ref "U1") (pin "22") (pinfunction "P0.06_22") (pintype "unspecified"))
    )
    (net (code "52") (name "QWIIC_SDA") (class "Default")
      (node (ref "J3") (pin "3") (pinfunction "3_3") (pintype "unspecified"))
      (node (ref "U1") (pin "24") (pinfunction "P0.08_24") (pintype "unspecified"))
    )
    (net (code "53") (name "RESET") (class "Default")
      (node (ref "J2L") (pin "46") (pinfunction "46_46") (pintype "unspecified"))
      (node (ref "J4") (pin "10") (pinfunction "~RESET~_10") (pintype "unspecified"))
      (node (ref "S2") (pin "2") (pinfunction "2_2") (pintype "unspecified"))
      (node (ref "S2") (pin "3") (pinfunction "3_3") (pintype "unspecified"))
      (node (ref "U1") (pin "40") (pinfunction "P0.18/RESET_40") (pintype "unspecified"))
    )
    (net (code "54") (name "RXD") (class "Default")
      (node (ref "J2L") (pin "21") (pinfunction "21_21") (pintype "unspecified"))
      (node (ref "J2L") (pin "22") (pinfunction "22_22") (pintype "unspecified"))
      (node (ref "U1") (pin "48") (pinfunction "P0.24_48") (pintype "unspecified"))
    )
    (net (code "55") (name "SCK") (class "Default")
      (node (ref "J2L") (pin "27") (pinfunction "27_27") (pintype "unspecified"))
      (node (ref "U1") (pin "36") (pinfunction "P0.14_36") (pintype "unspecified"))
    )
    (net (code "56") (name "SCL") (class "Default")
      (node (ref "J2R") (pin "4") (pinfunction "4_4") (pintype "unspecified"))
      (node (ref "U1") (pin "27") (pinfunction "P0.11_27") (pintype "unspecified"))
    )
    (net (code "57") (name "SDA") (class "Default")
      (node (ref "J2R") (pin "3") (pinfunction "3_3") (pintype "unspecified"))
      (node (ref "U1") (pin "29") (pinfunction "P0.12_29") (pintype "unspecified"))
    )
    (net (code "58") (name "SWCLK") (class "Default")
      (node (ref "J4") (pin "4") (pinfunction "SWDCLK/TCK_4") (pintype "unspecified"))
      (node (ref "U1") (pin "53") (pinfunction "SWDCLK_53") (pintype "unspecified"))
    )
    (net (code "59") (name "SWDIO") (class "Default")
      (node (ref "J4") (pin "2") (pinfunction "SWDIO/TMS_2") (pintype "unspecified"))
      (node (ref "U1") (pin "51") (pinfunction "SWDIO_51") (pintype "unspecified"))
    )
    (net (code "60") (name "SWITCH1") (class "Default")
      (node (ref "S3") (pin "1") (pinfunction "1_1") (pintype "unspecified"))
      (node (ref "S3") (pin "2") (pinfunction "2_2") (pintype "unspecified"))
      (node (ref "U1") (pin "50") (pinfunction "P1.02_50") (pintype "unspecified"))
    )
    (net (code "61") (name "SWITCH2") (class "Default")
      (node (ref "S4") (pin "1") (pinfunction "1_1") (pintype "unspecified"))
      (node (ref "S4") (pin "2") (pinfunction "2_2") (pintype "unspecified"))
      (node (ref "U1") (pin "58") (pinfunction "P1.07_58") (pintype "unspecified"))
    )
    (net (code "62") (name "SWO") (class "Default")
      (node (ref "J4") (pin "6") (pinfunction "SWO/TDO_6") (pintype "unspecified"))
      (node (ref "U1") (pin "47") (pinfunction "P1.00_47") (pintype "unspecified"))
    )
    (net (code "63") (name "TXD") (class "Default")
      (node (ref "J2L") (pin "19") (pinfunction "19_19") (pintype "unspecified"))
      (node (ref "J2L") (pin "20") (pinfunction "20_20") (pintype "unspecified"))
      (node (ref "U1") (pin "49") (pinfunction "P0.25_49") (pintype "unspecified"))
    )
    (net (code "64") (name "USBD+") (class "Default")
      (node (ref "J5") (pin "6") (pinfunction "DP1_6") (pintype "input"))
      (node (ref "J5") (pin "8") (pinfunction "DP2_8") (pintype "input"))
      (node (ref "R22") (pin "1") (pinfunction "1_1") (pintype "unspecified"))
      (node (ref "TP5") (pin "P$1") (pinfunction "1_P$1") (pintype "unspecified"))
    )
    (net (code "65") (name "USBD-") (class "Default")
      (node (ref "J5") (pin "5") (pinfunction "DN2_5") (pintype "input"))
      (node (ref "J5") (pin "7") (pinfunction "DN1_7") (pintype "input"))
      (node (ref "R21") (pin "1") (pinfunction "1_1") (pintype "unspecified"))
      (node (ref "TP6") (pin "P$1") (pinfunction "1_P$1") (pintype "unspecified"))
    )
    (net (code "66") (name "VBAT") (class "Default")
      (node (ref "C6") (pin "1") (pinfunction "1_1") (pintype "unspecified"))
      (node (ref "J1") (pin "1") (pinfunction "1_1") (pintype "unspecified"))
      (node (ref "J2R") (pin "14") (pinfunction "14_14") (pintype "unspecified"))
      (node (ref "Q3") (pin "3") (pinfunction "D_3") (pintype "unspecified"))
      (node (ref "R14") (pin "2") (pinfunction "2_2") (pintype "unspecified"))
      (node (ref "U2") (pin "3") (pinfunction "VBAT_3") (pintype "unspecified"))
    )
    (net (code "67") (name "VBUS") (class "Default")
      (node (ref "C5") (pin "1") (pinfunction "1_1") (pintype "unspecified"))
      (node (ref "D2") (pin "A") (pinfunction "A_A") (pintype "unspecified"))
      (node (ref "D6") (pin "A") (pinfunction "A_A") (pintype "unspecified"))
      (node (ref "J2R") (pin "12") (pinfunction "12_12") (pintype "unspecified"))
      (node (ref "J2R") (pin "2") (pinfunction "5V_2") (pintype "unspecified"))
      (node (ref "J5") (pin "11") (pinfunction "VBUS_11") (pintype "input"))
      (node (ref "J5") (pin "2") (pinfunction "VBUS_2") (pintype "input"))
      (node (ref "Q3") (pin "1") (pinfunction "G_1") (pintype "unspecified"))
      (node (ref "R2") (pin "2") (pinfunction "2_2") (pintype "unspecified"))
      (node (ref "U1") (pin "32") (pinfunction "VBUS_32") (pintype "unspecified"))
      (node (ref "U2") (pin "4") (pinfunction "VIN_4") (pintype "unspecified"))
    )
    (net (code "68") (name "VDIV") (class "Default")
      (node (ref "R14") (pin "1") (pinfunction "1_1") (pintype "unspecified"))
      (node (ref "R15") (pin "2") (pinfunction "2_2") (pintype "unspecified"))
      (node (ref "U1") (pin "10") (pinfunction "P0.29/AIN5_10") (pintype "unspecified"))
    )
    (net (code "69") (name "VIN") (class "Default")
      (node (ref "C3") (pin "1") (pinfunction "1_1") (pintype "unspecified"))
      (node (ref "D6") (pin "C") (pinfunction "C_C") (pintype "unspecified"))
      (node (ref "Q3") (pin "2") (pinfunction "S_2") (pintype "unspecified"))
      (node (ref "S1") (pin "3") (pinfunction "3_3") (pintype "unspecified"))
      (node (ref "TP1") (pin "P$1") (pinfunction "1_P$1") (pintype "unspecified"))
      (node (ref "U3") (pin "1") (pinfunction "IN_1") (pintype "unspecified"))
    )
    (net (code "70") (name "VOUT") (class "Default")
      (node (ref "C24") (pin "1") (pinfunction "1_1") (pintype "input"))
      (node (ref "C26") (pin "1") (pinfunction "1_1") (pintype "unspecified"))
      (node (ref "C4") (pin "1") (pinfunction "1_1") (pintype "unspecified"))
      (node (ref "D5") (pin "VCC") (pinfunction "VCC_VCC") (pintype "unspecified"))
      (node (ref "J2L") (pin "16") (pinfunction "16_16") (pintype "unspecified"))
      (node (ref "J2L") (pin "30") (pinfunction "30_30") (pintype "unspecified"))
      (node (ref "J2L") (pin "43") (pinfunction "43_43") (pintype "unspecified"))
      (node (ref "J2L") (pin "44") (pinfunction "44_44") (pintype "unspecified"))
      (node (ref "J2L") (pin "45") (pinfunction "45_45") (pintype "unspecified"))
      (node (ref "J3") (pin "2") (pinfunction "2_2") (pintype "unspecified"))
      (node (ref "U5") (pin "5") (pinfunction "OUT_5") (pintype "input"))
    )
    (net (code "71") (name "VOUT_EN") (class "Default")
      (node (ref "R24") (pin "1") (pinfunction "1_1") (pintype "unspecified"))
      (node (ref "TP3") (pin "P$1") (pinfunction "1_P$1") (pintype "unspecified"))
      (node (ref "U1") (pin "56") (pinfunction "P1.04_56") (pintype "unspecified"))
      (node (ref "U5") (pin "3") (pinfunction "EN_3") (pintype "input"))
    )
    (net (code "72") (name "unconnected-(D5-PadDO)") (class "Default")
      (node (ref "D5") (pin "DO") (pinfunction "DO_DO") (pintype "unspecified+no_connect"))
    )
    (net (code "73") (name "unconnected-(J1-Pad3)") (class "Default")
      (node (ref "J1") (pin "3") (pinfunction "3_3") (pintype "unspecified+no_connect"))
    )
    (net (code "74") (name "unconnected-(J1-Pad4)") (class "Default")
      (node (ref "J1") (pin "4") (pinfunction "4_4") (pintype "unspecified+no_connect"))
    )
    (net (code "75") (name "unconnected-(J4-KEY-Pad7)") (class "Default")
      (node (ref "J4") (pin "7") (pinfunction "KEY_7") (pintype "unspecified+no_connect"))
    )
    (net (code "76") (name "unconnected-(J4-NC{slash}TDI-Pad8)") (class "Default")
      (node (ref "J4") (pin "8") (pinfunction "NC/TDI_8") (pintype "unspecified+no_connect"))
    )
    (net (code "77") (name "unconnected-(J5-SBU1-Pad9)") (class "Default")
      (node (ref "J5") (pin "9") (pinfunction "SBU1_9") (pintype "input+no_connect"))
    )
    (net (code "78") (name "unconnected-(J5-SBU2-Pad3)") (class "Default")
      (node (ref "J5") (pin "3") (pinfunction "SBU2_3") (pintype "input+no_connect"))
    )
    (net (code "79") (name "unconnected-(J5-SHELL-Pad13)") (class "Default")
      (node (ref "J5") (pin "13") (pinfunction "SHELL_13") (pintype "input+no_connect"))
    )
    (net (code "80") (name "unconnected-(J5-SHELL-Pad14)") (class "Default")
      (node (ref "J5") (pin "14") (pinfunction "SHELL_14") (pintype "input+no_connect"))
    )
    (net (code "81") (name "unconnected-(S1-Pad4)") (class "Default")
      (node (ref "S1") (pin "4") (pinfunction "4_4") (pintype "unspecified+no_connect"))
    )
    (net (code "82") (name "unconnected-(S1-Pad5)") (class "Default")
      (node (ref "S1") (pin "5") (pinfunction "5_5") (pintype "unspecified+no_connect"))
    )
    (net (code "83") (name "unconnected-(S1-Pad6)") (class "Default")
      (node (ref "S1") (pin "6") (pinfunction "6_6") (pintype "unspecified+no_connect"))
    )
    (net (code "84") (name "unconnected-(S1-Pad7)") (class "Default")
      (node (ref "S1") (pin "7") (pinfunction "7_7") (pintype "unspecified+no_connect"))
    )
    (net (code "85") (name "unconnected-(S2-Pad4)") (class "Default")
      (node (ref "S2") (pin "4") (pinfunction "4_4") (pintype "unspecified+no_connect"))
    )
    (net (code "86") (name "unconnected-(S2-Pad5)") (class "Default")
      (node (ref "S2") (pin "5") (pinfunction "5_5") (pintype "unspecified+no_connect"))
    )
    (net (code "87") (name "unconnected-(U1-DCCH-Pad31)") (class "Default")
      (node (ref "U1") (pin "31") (pinfunction "DCCH_31") (pintype "unspecified+no_connect"))
    )
    (net (code "88") (name "unconnected-(U1-P1.06-Pad57)") (class "Default")
      (node (ref "U1") (pin "57") (pinfunction "P1.06_57") (pintype "unspecified+no_connect"))
    )
    (net (code "89") (name "unconnected-(U3-NC-Pad4)") (class "Default")
      (node (ref "U3") (pin "4") (pinfunction "NC_4") (pintype "unspecified+no_connect"))
    )
    (net (code "90") (name "unconnected-(U4-EP-Pad9)") (class "Default")
      (node (ref "U4") (pin "9") (pinfunction "EP_9") (pintype "unspecified+no_connect"))
    )
    (net (code "91") (name "unconnected-(U5-FLG-Pad4)") (class "Default")
      (node (ref "U5") (pin "4") (pinfunction "FLG_4") (pintype "input+no_connect"))
    )
    (net (code "92") (name "unconnected-(U5-NC-Pad6)") (class "Default")
      (node (ref "U5") (pin "6") (pinfunction "NC_6") (pintype "input+no_connect"))
    )
  )
)
